# UART.net
KiCad netlist of a schematic drawn in Altium Designer
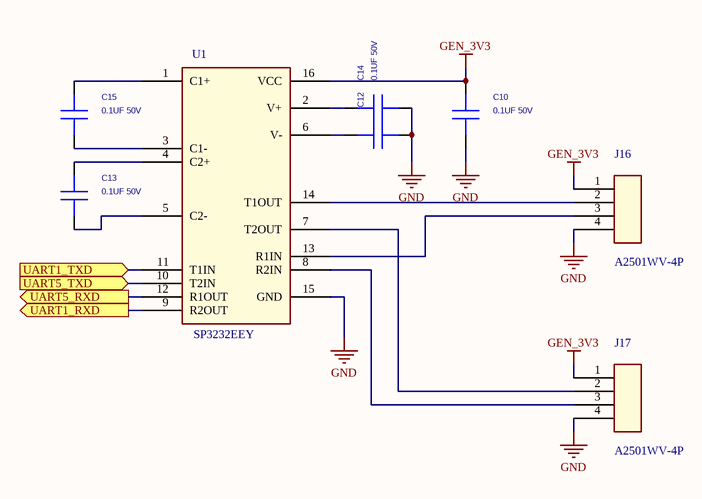
[diagram p0: UART.SchDoc]

(export (version "E")
  (design (tool "Eeschema 10.0.6"))
  (components
    (comp (ref "C10")
      (value "0.1UF 50V")
      (footprint "SC0603")
      (description "Capacitor, 0.1uF, 50V, 10%, X5R, 0603")
      (fields (field (name "VOLTAGE") "6.3V") (field (name "TOLERANCE") "10%"))
      (libsource (lib "MY-I.MX6-SCH_Library") (part "0.1uF-6.3V-10%-X5R-0402"))
    )
    (comp (ref "C12")
      (value "0.1UF 50V")
      (footprint "SC0603")
      (description "Capacitor, 0.1uF, 50V, 10%, X5R, 0603")
      (fields (field (name "VOLTAGE") "6.3V") (field (name "TOLERANCE") "10%"))
      (libsource (lib "MY-I.MX6-SCH_Library") (part "0.1uF-6.3V-10%-X5R-0402"))
    )
    (comp (ref "C13")
      (value "0.1UF 50V")
      (footprint "SC0603")
      (description "Capacitor, 0.1uF, 50V, 10%, X5R, 0603")
      (fields (field (name "VOLTAGE") "6.3V") (field (name "TOLERANCE") "10%"))
      (libsource (lib "MY-I.MX6-SCH_Library") (part "0.1uF-6.3V-10%-X5R-0402"))
    )
    (comp (ref "C14")
      (value "0.1UF 50V")
      (footprint "SC0603")
      (description "Capacitor, 0.1uF, 50V, 10%, X5R, 0603")
      (fields (field (name "VOLTAGE") "6.3V") (field (name "TOLERANCE") "10%"))
      (libsource (lib "MY-I.MX6-SCH_Library") (part "0.1uF-6.3V-10%-X5R-0402"))
    )
    (comp (ref "C15")
      (value "0.1UF 50V")
      (footprint "SC0603")
      (description "Capacitor, 0.1uF, 50V, 10%, X5R, 0603")
      (fields (field (name "VOLTAGE") "6.3V") (field (name "TOLERANCE") "10%"))
      (libsource (lib "MY-I.MX6-SCH_Library") (part "0.1uF-6.3V-10%-X5R-0402"))
    )
    (comp (ref "J16")
      (value "A2501WV-4P")
      (footprint "A2501WV-4P")
      (libsource (lib "MY-I.MX6-SCH_Library") (part "CON4"))
    )
    (comp (ref "J17")
      (value "A2501WV-4P")
      (footprint "A2501WV-4P")
      (libsource (lib "MY-I.MX6-SCH_Library") (part "CON4"))
    )
    (comp (ref "U1")
      (value "SP3232EEY")
      (footprint "TSSOP16-0P65-5P1X4P5")
      (libsource (lib "MY-I.MX6-SCH_Library") (part "SP3232EEY"))
    )
  )
  (nets
    (net (code "1") (name "/UART1_RXD") (class "Default")
      (node (ref "U1") (pin "9") (pinfunction "R2OUT_9") (pintype "passive"))
    )
    (net (code "2") (name "/UART1_TXD") (class "Default")
      (node (ref "U1") (pin "11") (pinfunction "T1IN_11") (pintype "passive"))
    )
    (net (code "3") (name "/UART5_RXD") (class "Default")
      (node (ref "U1") (pin "12") (pinfunction "R1OUT_12") (pintype "passive"))
    )
    (net (code "4") (name "/UART5_TXD") (class "Default")
      (node (ref "U1") (pin "10") (pinfunction "T2IN_10") (pintype "passive"))
    )
    (net (code "5") (name "GEN_3V3") (class "Default")
      (node (ref "C10") (pin "1") (pinfunction "1_1") (pintype "passive"))
      (node (ref "J16") (pin "1") (pinfunction "1_1") (pintype "passive"))
      (node (ref "J17") (pin "1") (pinfunction "1_1") (pintype "passive"))
      (node (ref "U1") (pin "16") (pinfunction "VCC_16") (pintype "passive"))
    )
    (net (code "6") (name "GND") (class "Default")
      (node (ref "C10") (pin "2") (pinfunction "2_2") (pintype "passive"))
      (node (ref "C12") (pin "2") (pinfunction "2_2") (pintype "passive"))
      (node (ref "C14") (pin "2") (pinfunction "2_2") (pintype "passive"))
      (node (ref "J16") (pin "4") (pinfunction "4_4") (pintype "passive"))
      (node (ref "J17") (pin "4") (pinfunction "4_4") (pintype "passive"))
      (node (ref "U1") (pin "15") (pinfunction "GND_15") (pintype "passive"))
    )
    (net (code "7") (name "Net-(U1-C1+)") (class "Default")
      (node (ref "C15") (pin "1") (pinfunction "1_1") (pintype "passive"))
      (node (ref "U1") (pin "1") (pinfunction "C1+_1") (pintype "passive"))
    )
    (net (code "8") (name "Net-(U1-C1-)") (class "Default")
      (node (ref "C15") (pin "2") (pinfunction "2_2") (pintype "passive"))
      (node (ref "U1") (pin "3") (pinfunction "C1-_3") (pintype "passive"))
    )
    (net (code "9") (name "Net-(U1-C2+)") (class "Default")
      (node (ref "C13") (pin "1") (pinfunction "1_1") (pintype "passive"))
      (node (ref "U1") (pin "4") (pinfunction "C2+_4") (pintype "passive"))
    )
    (net (code "10") (name "Net-(U1-C2-)") (class "Default")
      (node (ref "C13") (pin "2") (pinfunction "2_2") (pintype "passive"))
      (node (ref "U1") (pin "5") (pinfunction "C2-_5") (pintype "passive"))
    )
    (net (code "11") (name "Net-(U1-R1IN)") (class "Default")
      (node (ref "J16") (pin "3") (pinfunction "3_3") (pintype "passive"))
      (node (ref "U1") (pin "13") (pinfunction "R1IN_13") (pintype "passive"))
    )
    (net (code "12") (name "Net-(U1-R2IN)") (class "Default")
      (node (ref "J17") (pin "3") (pinfunction "3_3") (pintype "passive"))
      (node (ref "U1") (pin "8") (pinfunction "R2IN_8") (pintype "passive"))
    )
    (net (code "13") (name "Net-(U1-T1OUT)") (class "Default")
      (node (ref "J16") (pin "2") (pinfunction "2_2") (pintype "passive"))
      (node (ref "U1") (pin "14") (pinfunction "T1OUT_14") (pintype "passive"))
    )
    (net (code "14") (name "Net-(U1-T2OUT)") (class "Default")
      (node (ref "J17") (pin "2") (pinfunction "2_2") (pintype "passive"))
      (node (ref "U1") (pin "7") (pinfunction "T2OUT_7") (pintype "passive"))
    )
    (net (code "15") (name "Net-(U1-V+)") (class "Default")
      (node (ref "C14") (pin "1") (pinfunction "1_1") (pintype "passive"))
      (node (ref "U1") (pin "2") (pinfunction "V+_2") (pintype "passive"))
    )
    (net (code "16") (name "Net-(U1-V-)") (class "Default")
      (node (ref "C12") (pin "1") (pinfunction "1_1") (pintype "passive"))
      (node (ref "U1") (pin "6") (pinfunction "V-_6") (pintype "passive"))
    )
  )
)
